# pic_can_x10.net
KiCad netlist of a schematic drawn in EAGLE
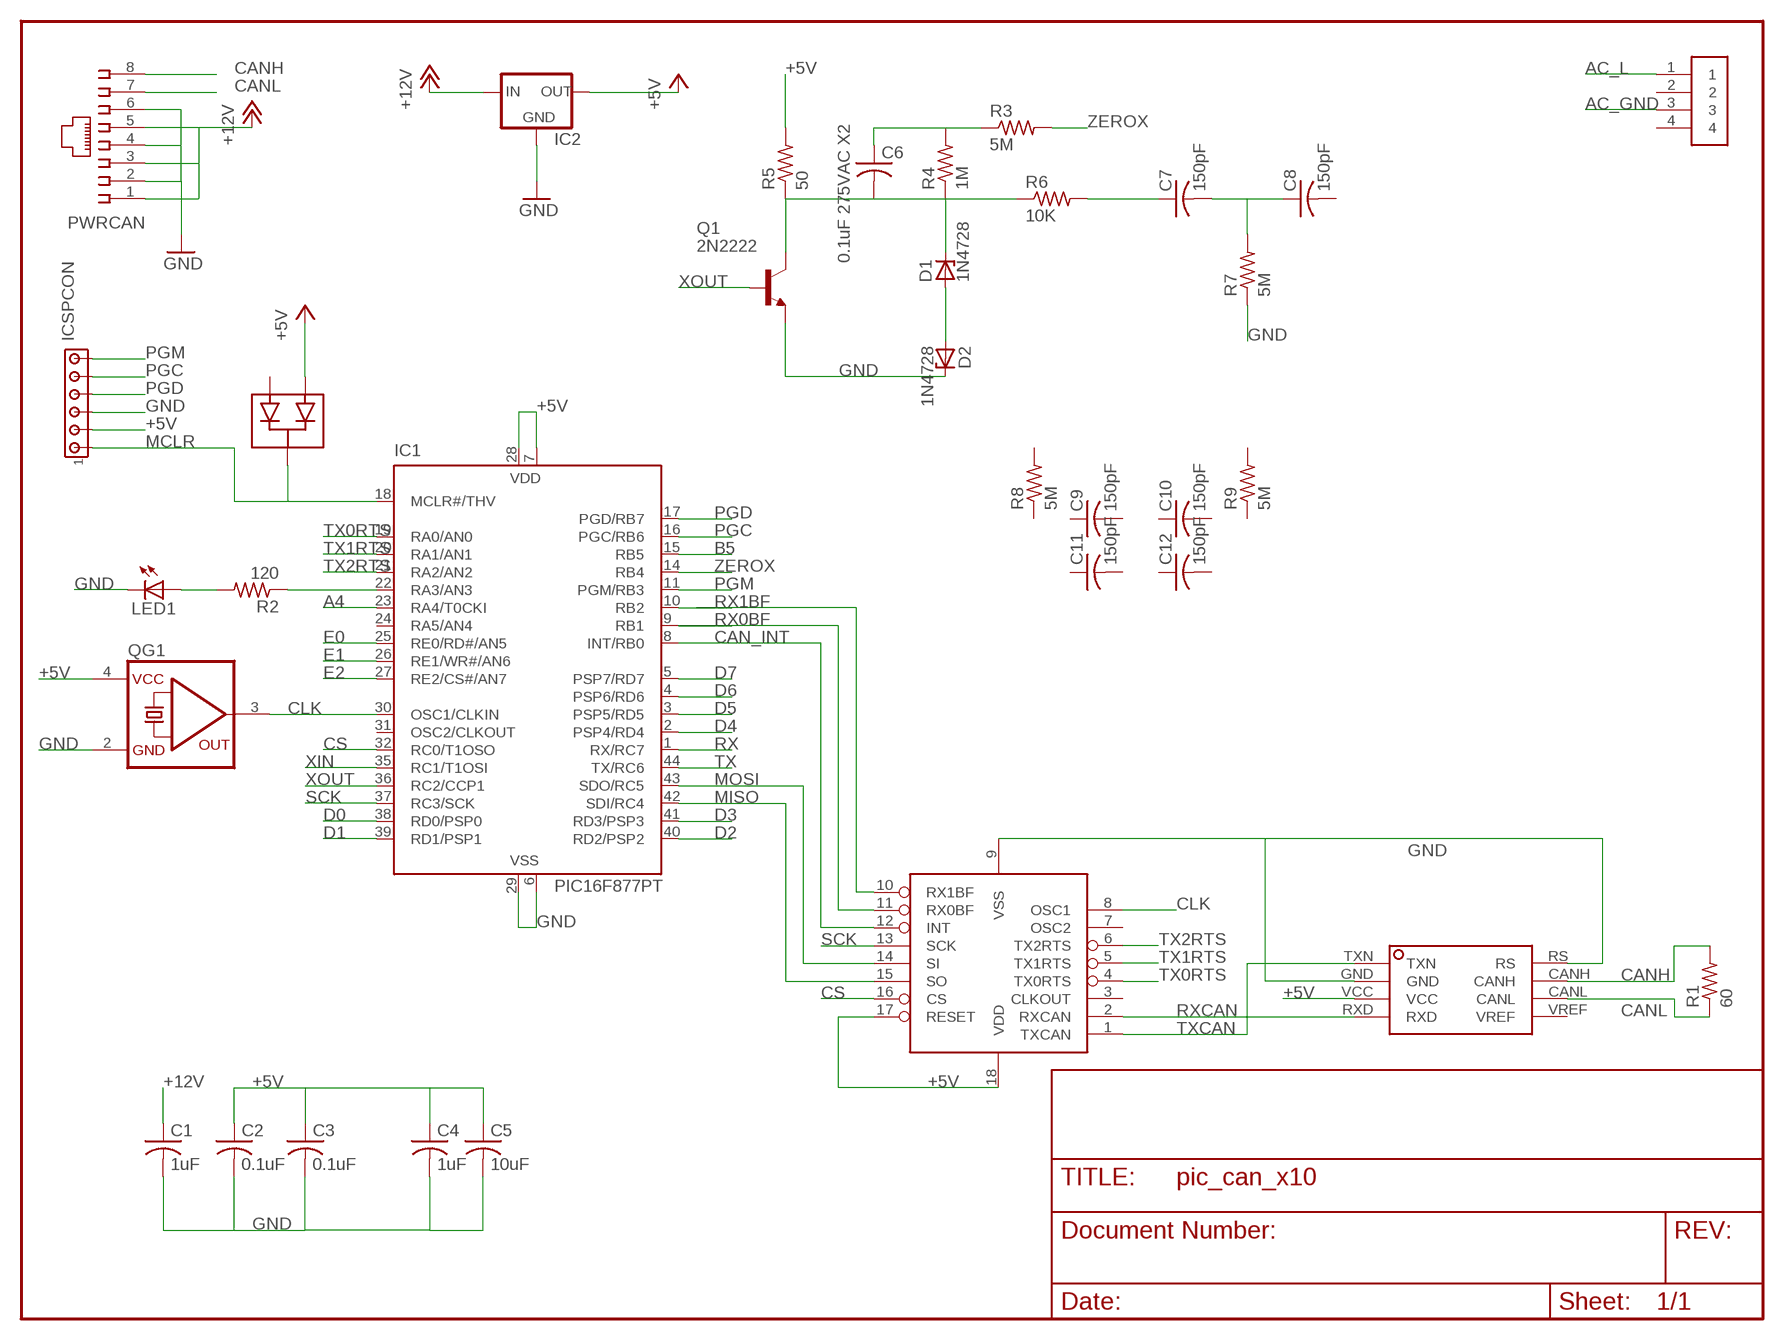
[diagram p0: schematic, sheet 1]

(export (version "E")
  (design (tool "Eeschema 10.0.6"))
  (components
    (comp (ref "C1")
      (value "1uF")
      (footprint "eagle-import:C0805")
      (libsource (lib "eagle-import") (part "C-USC0805"))
    )
    (comp (ref "C2")
      (value "0.1uF")
      (footprint "eagle-import:C0805")
      (libsource (lib "eagle-import") (part "C-USC0805"))
    )
    (comp (ref "C3")
      (value "0.1uF")
      (footprint "eagle-import:C0805")
      (libsource (lib "eagle-import") (part "C-USC0805"))
    )
    (comp (ref "C4")
      (value "1uF")
      (footprint "eagle-import:C0805")
      (libsource (lib "eagle-import") (part "C-USC0805"))
    )
    (comp (ref "C5")
      (value "10uF")
      (footprint "eagle-import:C1206")
      (libsource (lib "eagle-import") (part "C-USC1206"))
    )
    (comp (ref "C6")
      (value "0.1uF 275VAC X2")
      (footprint "eagle-import:C0805")
      (libsource (lib "eagle-import") (part "C-USC0805"))
    )
    (comp (ref "C7")
      (value "150pF")
      (footprint "eagle-import:C0805")
      (libsource (lib "eagle-import") (part "C-USC0805"))
    )
    (comp (ref "C8")
      (value "150pF")
      (footprint "eagle-import:C0805")
      (libsource (lib "eagle-import") (part "C-USC0805"))
    )
    (comp (ref "C9")
      (value "150pF")
      (footprint "eagle-import:C0805")
      (libsource (lib "eagle-import") (part "C-USC0805"))
    )
    (comp (ref "C10")
      (value "150pF")
      (footprint "eagle-import:C0805")
      (libsource (lib "eagle-import") (part "C-USC0805"))
    )
    (comp (ref "C11")
      (value "150pF")
      (footprint "eagle-import:C0805")
      (libsource (lib "eagle-import") (part "C-USC0805"))
    )
    (comp (ref "C12")
      (value "150pF")
      (footprint "eagle-import:C0805")
      (libsource (lib "eagle-import") (part "C-USC0805"))
    )
    (comp (ref "D1")
      (value "1N4728")
      (footprint "eagle-import:DO41Z10")
      (libsource (lib "eagle-import") (part "1N4728"))
    )
    (comp (ref "D2")
      (value "1N4728")
      (footprint "eagle-import:DO41Z10")
      (libsource (lib "eagle-import") (part "1N4728"))
    )
    (comp (ref "IC1")
      (value "PIC16F877PT")
      (footprint "eagle-import:TQFP44")
      (libsource (lib "eagle-import") (part "PIC16F87PT7"))
    )
    (comp (ref "IC2")
      (value "78XXL")
      (footprint "eagle-import:78XXL")
      (libsource (lib "eagle-import") (part "78XXL"))
    )
    (comp (ref "IC3")
      (value "UC5350D")
      (footprint "eagle-import:SOIC8")
      (libsource (lib "eagle-import") (part "UC5350D"))
    )
    (comp (ref "ICSPCON")
      (value "MTA06-100")
      (footprint "eagle-import:10X06MTA")
      (libsource (lib "eagle-import") (part "MTA06-100"))
    )
    (comp (ref "LED1")
      (value "LEDCHIPLED_0805")
      (footprint "eagle-import:CHIPLED_0805")
      (libsource (lib "eagle-import") (part "LEDCHIPLED_0805"))
    )
    (comp (ref "MCP1")
      (value "MCP2510-I/SO")
      (footprint "eagle-import:SO-18W")
      (libsource (lib "eagle-import") (part "MCP2510-I/SO"))
    )
    (comp (ref "PWRCAN")
      (value "555166-1")
      (footprint "eagle-import:555166-1")
      (libsource (lib "eagle-import") (part "555166-1"))
    )
    (comp (ref "Q1")
      (value "2N2222")
      (footprint "eagle-import:TO18")
      (libsource (lib "eagle-import") (part "2N2222"))
    )
    (comp (ref "QG1")
      (value "SG531")
      (footprint "eagle-import:DIL08-4")
      (libsource (lib "eagle-import") (part "SG531"))
    )
    (comp (ref "R1")
      (value "60")
      (footprint "eagle-import:R0805")
      (libsource (lib "eagle-import") (part "R-US_R0805"))
    )
    (comp (ref "R2")
      (value "120")
      (footprint "eagle-import:R0805")
      (libsource (lib "eagle-import") (part "R-US_R0805"))
    )
    (comp (ref "R3")
      (value "5M")
      (footprint "eagle-import:R0805")
      (libsource (lib "eagle-import") (part "R-US_R0805"))
    )
    (comp (ref "R4")
      (value "1M")
      (footprint "eagle-import:R0805")
      (libsource (lib "eagle-import") (part "R-US_R0805"))
    )
    (comp (ref "R5")
      (value "50")
      (footprint "eagle-import:R0805")
      (libsource (lib "eagle-import") (part "R-US_R0805"))
    )
    (comp (ref "R6")
      (value "10K")
      (footprint "eagle-import:R0805")
      (libsource (lib "eagle-import") (part "R-US_R0805"))
    )
    (comp (ref "R7")
      (value "5M")
      (footprint "eagle-import:R0805")
      (libsource (lib "eagle-import") (part "R-US_R0805"))
    )
    (comp (ref "R8")
      (value "5M")
      (footprint "eagle-import:R0805")
      (libsource (lib "eagle-import") (part "R-US_R0805"))
    )
    (comp (ref "R9")
      (value "5M")
      (footprint "eagle-import:R0805")
      (libsource (lib "eagle-import") (part "R-US_R0805"))
    )
    (comp (ref "U$1")
      (value "MPT0.5/4-2.54\"")
      (footprint "eagle-import:MPT0.5_4-2.54")
      (libsource (lib "eagle-import") (part "MPT0.5/4-2.54{dblquote}"))
    )
    (comp (ref "U$2")
      (value "BAV70_")
      (footprint "eagle-import:SOT-23")
      (libsource (lib "eagle-import") (part "BAV70_"))
    )
  )
  (nets
    (net (code "1") (name "+5V") (class "Default")
      (node (ref "C2") (pin "1") (pinfunction "1_1") (pintype "passive"))
      (node (ref "C3") (pin "1") (pinfunction "1_1") (pintype "passive"))
      (node (ref "C4") (pin "1") (pinfunction "1_1") (pintype "passive"))
      (node (ref "C5") (pin "1") (pinfunction "1_1") (pintype "passive"))
      (node (ref "IC1") (pin "28") (pinfunction "VDD_28") (pintype "power_in"))
      (node (ref "IC1") (pin "7") (pinfunction "VDD_7") (pintype "power_in"))
      (node (ref "IC2") (pin "OUT") (pinfunction "OUT_OUT") (pintype "passive"))
      (node (ref "IC3") (pin "VCC") (pinfunction "VCC_VCC") (pintype "bidirectional"))
      (node (ref "ICSPCON") (pin "5") (pinfunction "2_5") (pintype "passive"))
      (node (ref "MCP1") (pin "17") (pinfunction "RESET_17") (pintype "input"))
      (node (ref "MCP1") (pin "18") (pinfunction "VDD_18") (pintype "power_in"))
      (node (ref "QG1") (pin "4") (pinfunction "VCC_4") (pintype "power_in"))
      (node (ref "R5") (pin "2") (pinfunction "2_2") (pintype "passive"))
      (node (ref "U$2") (pin "1") (pinfunction "A1_1") (pintype "bidirectional"))
    )
    (net (code "2") (name "+12V") (class "Default")
      (node (ref "C1") (pin "1") (pinfunction "1_1") (pintype "passive"))
      (node (ref "IC2") (pin "IN") (pinfunction "IN_IN") (pintype "input"))
      (node (ref "PWRCAN") (pin "1") (pinfunction "1_1") (pintype "passive"))
      (node (ref "PWRCAN") (pin "3") (pinfunction "3_3") (pintype "passive"))
      (node (ref "PWRCAN") (pin "5") (pinfunction "5_5") (pintype "passive"))
    )
    (net (code "3") (name "/A4") (class "Default")
      (node (ref "IC1") (pin "23") (pinfunction "RA4/T0CKI_23") (pintype "bidirectional"))
    )
    (net (code "4") (name "/AC_GND") (class "Default")
      (node (ref "U$1") (pin "3") (pinfunction "3_3") (pintype "bidirectional"))
    )
    (net (code "5") (name "/AC_L") (class "Default")
      (node (ref "C6") (pin "1") (pinfunction "1_1") (pintype "passive"))
      (node (ref "R3") (pin "1") (pinfunction "1_1") (pintype "passive"))
      (node (ref "R4") (pin "2") (pinfunction "2_2") (pintype "passive"))
      (node (ref "U$1") (pin "1") (pinfunction "1_1") (pintype "bidirectional"))
    )
    (net (code "6") (name "/B5") (class "Default")
      (node (ref "IC1") (pin "15") (pinfunction "RB5_15") (pintype "bidirectional"))
    )
    (net (code "7") (name "/CANH") (class "Default")
      (node (ref "IC3") (pin "CANH") (pinfunction "CANH_CANH") (pintype "bidirectional"))
      (node (ref "PWRCAN") (pin "8") (pinfunction "8_8") (pintype "passive"))
      (node (ref "R1") (pin "2") (pinfunction "2_2") (pintype "passive"))
    )
    (net (code "8") (name "/CANL") (class "Default")
      (node (ref "IC3") (pin "CANL") (pinfunction "CANL_CANL") (pintype "bidirectional"))
      (node (ref "PWRCAN") (pin "7") (pinfunction "7_7") (pintype "passive"))
      (node (ref "R1") (pin "1") (pinfunction "1_1") (pintype "passive"))
    )
    (net (code "9") (name "/CAN_INT") (class "Default")
      (node (ref "IC1") (pin "8") (pinfunction "INT/RB0_8") (pintype "bidirectional"))
      (node (ref "MCP1") (pin "12") (pinfunction "INT_12") (pintype "output"))
    )
    (net (code "10") (name "/CLK") (class "Default")
      (node (ref "IC1") (pin "30") (pinfunction "OSC1/CLKIN_30") (pintype "input"))
      (node (ref "MCP1") (pin "8") (pinfunction "OSC1_8") (pintype "input"))
      (node (ref "QG1") (pin "3") (pinfunction "OUT_3") (pintype "output"))
    )
    (net (code "11") (name "/CS") (class "Default")
      (node (ref "IC1") (pin "32") (pinfunction "RC0/T1OSO_32") (pintype "bidirectional"))
      (node (ref "MCP1") (pin "16") (pinfunction "CS_16") (pintype "input"))
    )
    (net (code "12") (name "/D0") (class "Default")
      (node (ref "IC1") (pin "38") (pinfunction "RD0/PSP0_38") (pintype "bidirectional"))
    )
    (net (code "13") (name "/D1") (class "Default")
      (node (ref "IC1") (pin "39") (pinfunction "RD1/PSP1_39") (pintype "bidirectional"))
    )
    (net (code "14") (name "/D2") (class "Default")
      (node (ref "IC1") (pin "40") (pinfunction "RD2/PSP2_40") (pintype "bidirectional"))
    )
    (net (code "15") (name "/D3") (class "Default")
      (node (ref "IC1") (pin "41") (pinfunction "RD3/PSP3_41") (pintype "bidirectional"))
    )
    (net (code "16") (name "/D4") (class "Default")
      (node (ref "IC1") (pin "2") (pinfunction "PSP4/RD4_2") (pintype "bidirectional"))
    )
    (net (code "17") (name "/D5") (class "Default")
      (node (ref "IC1") (pin "3") (pinfunction "PSP5/RD5_3") (pintype "bidirectional"))
    )
    (net (code "18") (name "/D6") (class "Default")
      (node (ref "IC1") (pin "4") (pinfunction "PSP6/RD6_4") (pintype "bidirectional"))
    )
    (net (code "19") (name "/D7") (class "Default")
      (node (ref "IC1") (pin "5") (pinfunction "PSP7/RD7_5") (pintype "bidirectional"))
    )
    (net (code "20") (name "/E0") (class "Default")
      (node (ref "IC1") (pin "25") (pinfunction "RE0/RD#/AN5_25") (pintype "bidirectional"))
    )
    (net (code "21") (name "/E1") (class "Default")
      (node (ref "IC1") (pin "26") (pinfunction "RE1/WR#/AN6_26") (pintype "bidirectional"))
    )
    (net (code "22") (name "/E2") (class "Default")
      (node (ref "IC1") (pin "27") (pinfunction "RE2/CS#/AN7_27") (pintype "bidirectional"))
    )
    (net (code "23") (name "/MCLR") (class "Default")
      (node (ref "IC1") (pin "18") (pinfunction "MCLR#/THV_18") (pintype "input"))
      (node (ref "ICSPCON") (pin "6") (pinfunction "1_6") (pintype "passive"))
      (node (ref "U$2") (pin "3") (pinfunction "C_3") (pintype "bidirectional"))
    )
    (net (code "24") (name "/MISO") (class "Default")
      (node (ref "IC1") (pin "42") (pinfunction "SDI/RC4_42") (pintype "bidirectional"))
      (node (ref "MCP1") (pin "15") (pinfunction "SO_15") (pintype "output"))
    )
    (net (code "25") (name "/MOSI") (class "Default")
      (node (ref "IC1") (pin "43") (pinfunction "SDO/RC5_43") (pintype "bidirectional"))
      (node (ref "MCP1") (pin "14") (pinfunction "SI_14") (pintype "input"))
    )
    (net (code "26") (name "/PGC") (class "Default")
      (node (ref "IC1") (pin "16") (pinfunction "PGC/RB6_16") (pintype "bidirectional"))
      (node (ref "ICSPCON") (pin "2") (pinfunction "5_2") (pintype "passive"))
    )
    (net (code "27") (name "/PGD") (class "Default")
      (node (ref "IC1") (pin "17") (pinfunction "PGD/RB7_17") (pintype "bidirectional"))
      (node (ref "ICSPCON") (pin "3") (pinfunction "4_3") (pintype "passive"))
    )
    (net (code "28") (name "/PGM") (class "Default")
      (node (ref "IC1") (pin "11") (pinfunction "PGM/RB3_11") (pintype "bidirectional"))
      (node (ref "ICSPCON") (pin "1") (pinfunction "6_1") (pintype "passive"))
    )
    (net (code "29") (name "/RX") (class "Default")
      (node (ref "IC1") (pin "1") (pinfunction "RX/RC7_1") (pintype "bidirectional"))
    )
    (net (code "30") (name "/RX0BF") (class "Default")
      (node (ref "IC1") (pin "9") (pinfunction "RB1_9") (pintype "bidirectional"))
      (node (ref "MCP1") (pin "11") (pinfunction "RX0BF_11") (pintype "output"))
    )
    (net (code "31") (name "/RX1BF") (class "Default")
      (node (ref "IC1") (pin "10") (pinfunction "RB2_10") (pintype "bidirectional"))
      (node (ref "MCP1") (pin "10") (pinfunction "RX1BF_10") (pintype "output"))
    )
    (net (code "32") (name "/RXCAN") (class "Default")
      (node (ref "IC3") (pin "RXD") (pinfunction "RXD_RXD") (pintype "bidirectional"))
      (node (ref "MCP1") (pin "2") (pinfunction "RXCAN_2") (pintype "input"))
    )
    (net (code "33") (name "/SCK") (class "Default")
      (node (ref "IC1") (pin "37") (pinfunction "RC3/SCK_37") (pintype "bidirectional"))
      (node (ref "MCP1") (pin "13") (pinfunction "SCK_13") (pintype "input"))
    )
    (net (code "34") (name "/TX") (class "Default")
      (node (ref "IC1") (pin "44") (pinfunction "TX/RC6_44") (pintype "bidirectional"))
    )
    (net (code "35") (name "/TX0RTS") (class "Default")
      (node (ref "IC1") (pin "19") (pinfunction "RA0/AN0_19") (pintype "bidirectional"))
      (node (ref "MCP1") (pin "4") (pinfunction "TX0RTS_4") (pintype "input"))
    )
    (net (code "36") (name "/TX1RTS") (class "Default")
      (node (ref "IC1") (pin "20") (pinfunction "RA1/AN1_20") (pintype "bidirectional"))
      (node (ref "MCP1") (pin "5") (pinfunction "TX1RTS_5") (pintype "input"))
    )
    (net (code "37") (name "/TX2RTS") (class "Default")
      (node (ref "IC1") (pin "21") (pinfunction "RA2/AN2_21") (pintype "bidirectional"))
      (node (ref "MCP1") (pin "6") (pinfunction "TX2RTS_6") (pintype "input"))
    )
    (net (code "38") (name "/TXCAN") (class "Default")
      (node (ref "IC3") (pin "TXN") (pinfunction "TXN_TXN") (pintype "bidirectional"))
      (node (ref "MCP1") (pin "1") (pinfunction "TXCAN_1") (pintype "output"))
    )
    (net (code "39") (name "/XIN") (class "Default")
      (node (ref "IC1") (pin "35") (pinfunction "RC1/T1OSI_35") (pintype "bidirectional"))
    )
    (net (code "40") (name "/XOUT") (class "Default")
      (node (ref "IC1") (pin "36") (pinfunction "RC2/CCP1_36") (pintype "bidirectional"))
      (node (ref "Q1") (pin "2") (pinfunction "B_2") (pintype "passive"))
    )
    (net (code "41") (name "/ZEROX") (class "Default")
      (node (ref "IC1") (pin "14") (pinfunction "RB4_14") (pintype "bidirectional"))
      (node (ref "R3") (pin "2") (pinfunction "2_2") (pintype "passive"))
    )
    (net (code "42") (name "GND") (class "Default")
      (node (ref "C1") (pin "2") (pinfunction "2_2") (pintype "passive"))
      (node (ref "C2") (pin "2") (pinfunction "2_2") (pintype "passive"))
      (node (ref "C3") (pin "2") (pinfunction "2_2") (pintype "passive"))
      (node (ref "C4") (pin "2") (pinfunction "2_2") (pintype "passive"))
      (node (ref "C5") (pin "2") (pinfunction "2_2") (pintype "passive"))
      (node (ref "D2") (pin "C") (pinfunction "C_C") (pintype "passive"))
      (node (ref "IC1") (pin "29") (pinfunction "VSS_29") (pintype "power_in"))
      (node (ref "IC1") (pin "6") (pinfunction "VSS_6") (pintype "power_in"))
      (node (ref "IC2") (pin "GND") (pinfunction "GND_GND") (pintype "input"))
      (node (ref "IC3") (pin "GND") (pinfunction "GND_GND") (pintype "bidirectional"))
      (node (ref "IC3") (pin "RS") (pinfunction "RS_RS") (pintype "bidirectional"))
      (node (ref "ICSPCON") (pin "4") (pinfunction "3_4") (pintype "passive"))
      (node (ref "LED1") (pin "C") (pinfunction "C_C") (pintype "passive"))
      (node (ref "MCP1") (pin "9") (pinfunction "VSS_9") (pintype "power_in"))
      (node (ref "PWRCAN") (pin "2") (pinfunction "2_2") (pintype "passive"))
      (node (ref "PWRCAN") (pin "4") (pinfunction "4_4") (pintype "passive"))
      (node (ref "PWRCAN") (pin "6") (pinfunction "6_6") (pintype "passive"))
      (node (ref "Q1") (pin "1") (pinfunction "E_1") (pintype "passive"))
      (node (ref "QG1") (pin "2") (pinfunction "GND_2") (pintype "power_in"))
      (node (ref "R7") (pin "1") (pinfunction "1_1") (pintype "passive"))
    )
    (net (code "43") (name "Net-(C7-Pad1)") (class "Default")
      (node (ref "C7") (pin "1") (pinfunction "1_1") (pintype "passive"))
      (node (ref "R6") (pin "2") (pinfunction "2_2") (pintype "passive"))
    )
    (net (code "44") (name "Net-(C7-Pad2)") (class "Default")
      (node (ref "C7") (pin "2") (pinfunction "2_2") (pintype "passive"))
      (node (ref "C8") (pin "1") (pinfunction "1_1") (pintype "passive"))
      (node (ref "R7") (pin "2") (pinfunction "2_2") (pintype "passive"))
    )
    (net (code "45") (name "Net-(D1-PadA)") (class "Default")
      (node (ref "D1") (pin "A") (pinfunction "A_A") (pintype "passive"))
      (node (ref "D2") (pin "A") (pinfunction "A_A") (pintype "passive"))
    )
    (net (code "46") (name "Net-(IC1-RA3{slash}AN3)") (class "Default")
      (node (ref "IC1") (pin "22") (pinfunction "RA3/AN3_22") (pintype "bidirectional"))
      (node (ref "R2") (pin "1") (pinfunction "1_1") (pintype "passive"))
    )
    (net (code "47") (name "Net-(LED1-PadA)") (class "Default")
      (node (ref "LED1") (pin "A") (pinfunction "A_A") (pintype "passive"))
      (node (ref "R2") (pin "2") (pinfunction "2_2") (pintype "passive"))
    )
    (net (code "48") (name "Net-(Q1-C)") (class "Default")
      (node (ref "C6") (pin "2") (pinfunction "2_2") (pintype "passive"))
      (node (ref "D1") (pin "C") (pinfunction "C_C") (pintype "passive"))
      (node (ref "Q1") (pin "3") (pinfunction "C_3") (pintype "passive"))
      (node (ref "R4") (pin "1") (pinfunction "1_1") (pintype "passive"))
      (node (ref "R5") (pin "1") (pinfunction "1_1") (pintype "passive"))
      (node (ref "R6") (pin "1") (pinfunction "1_1") (pintype "passive"))
    )
    (net (code "49") (name "unconnected-(C8-Pad2)") (class "Default")
      (node (ref "C8") (pin "2") (pinfunction "2_2") (pintype "passive"))
    )
    (net (code "50") (name "unconnected-(C9-Pad1)") (class "Default")
      (node (ref "C9") (pin "1") (pinfunction "1_1") (pintype "passive"))
    )
    (net (code "51") (name "unconnected-(C9-Pad2)") (class "Default")
      (node (ref "C9") (pin "2") (pinfunction "2_2") (pintype "passive"))
    )
    (net (code "52") (name "unconnected-(C10-Pad1)") (class "Default")
      (node (ref "C10") (pin "1") (pinfunction "1_1") (pintype "passive"))
    )
    (net (code "53") (name "unconnected-(C10-Pad2)") (class "Default")
      (node (ref "C10") (pin "2") (pinfunction "2_2") (pintype "passive"))
    )
    (net (code "54") (name "unconnected-(C11-Pad1)") (class "Default")
      (node (ref "C11") (pin "1") (pinfunction "1_1") (pintype "passive"))
    )
    (net (code "55") (name "unconnected-(C11-Pad2)") (class "Default")
      (node (ref "C11") (pin "2") (pinfunction "2_2") (pintype "passive"))
    )
    (net (code "56") (name "unconnected-(C12-Pad1)") (class "Default")
      (node (ref "C12") (pin "1") (pinfunction "1_1") (pintype "passive"))
    )
    (net (code "57") (name "unconnected-(C12-Pad2)") (class "Default")
      (node (ref "C12") (pin "2") (pinfunction "2_2") (pintype "passive"))
    )
    (net (code "58") (name "unconnected-(IC1-OSC2{slash}CLKOUT-Pad31)") (class "Default")
      (node (ref "IC1") (pin "31") (pinfunction "OSC2/CLKOUT_31") (pintype "output"))
    )
    (net (code "59") (name "unconnected-(IC1-RA5{slash}AN4-Pad24)") (class "Default")
      (node (ref "IC1") (pin "24") (pinfunction "RA5/AN4_24") (pintype "bidirectional"))
    )
    (net (code "60") (name "unconnected-(IC3-PadVREF)") (class "Default")
      (node (ref "IC3") (pin "VREF") (pinfunction "VREF_VREF") (pintype "bidirectional"))
    )
    (net (code "61") (name "unconnected-(MCP1-CLKOUT-Pad3)") (class "Default")
      (node (ref "MCP1") (pin "3") (pinfunction "CLKOUT_3") (pintype "output"))
    )
    (net (code "62") (name "unconnected-(MCP1-OSC2-Pad7)") (class "Default")
      (node (ref "MCP1") (pin "7") (pinfunction "OSC2_7") (pintype "output"))
    )
    (net (code "63") (name "unconnected-(R8-Pad1)") (class "Default")
      (node (ref "R8") (pin "1") (pinfunction "1_1") (pintype "passive"))
    )
    (net (code "64") (name "unconnected-(R8-Pad2)") (class "Default")
      (node (ref "R8") (pin "2") (pinfunction "2_2") (pintype "passive"))
    )
    (net (code "65") (name "unconnected-(R9-Pad1)") (class "Default")
      (node (ref "R9") (pin "1") (pinfunction "1_1") (pintype "passive"))
    )
    (net (code "66") (name "unconnected-(R9-Pad2)") (class "Default")
      (node (ref "R9") (pin "2") (pinfunction "2_2") (pintype "passive"))
    )
    (net (code "67") (name "unconnected-(U$1-Pad2)") (class "Default")
      (node (ref "U$1") (pin "2") (pinfunction "2_2") (pintype "bidirectional"))
    )
    (net (code "68") (name "unconnected-(U$1-Pad4)") (class "Default")
      (node (ref "U$1") (pin "4") (pinfunction "4_4") (pintype "bidirectional"))
    )
    (net (code "69") (name "unconnected-(U$2-A2-Pad2)") (class "Default")
      (node (ref "U$2") (pin "2") (pinfunction "A2_2") (pintype "bidirectional"))
    )
  )
)
